# QSFP_Cages_Connectors.net
KiCad netlist of a schematic drawn in Altium Designer
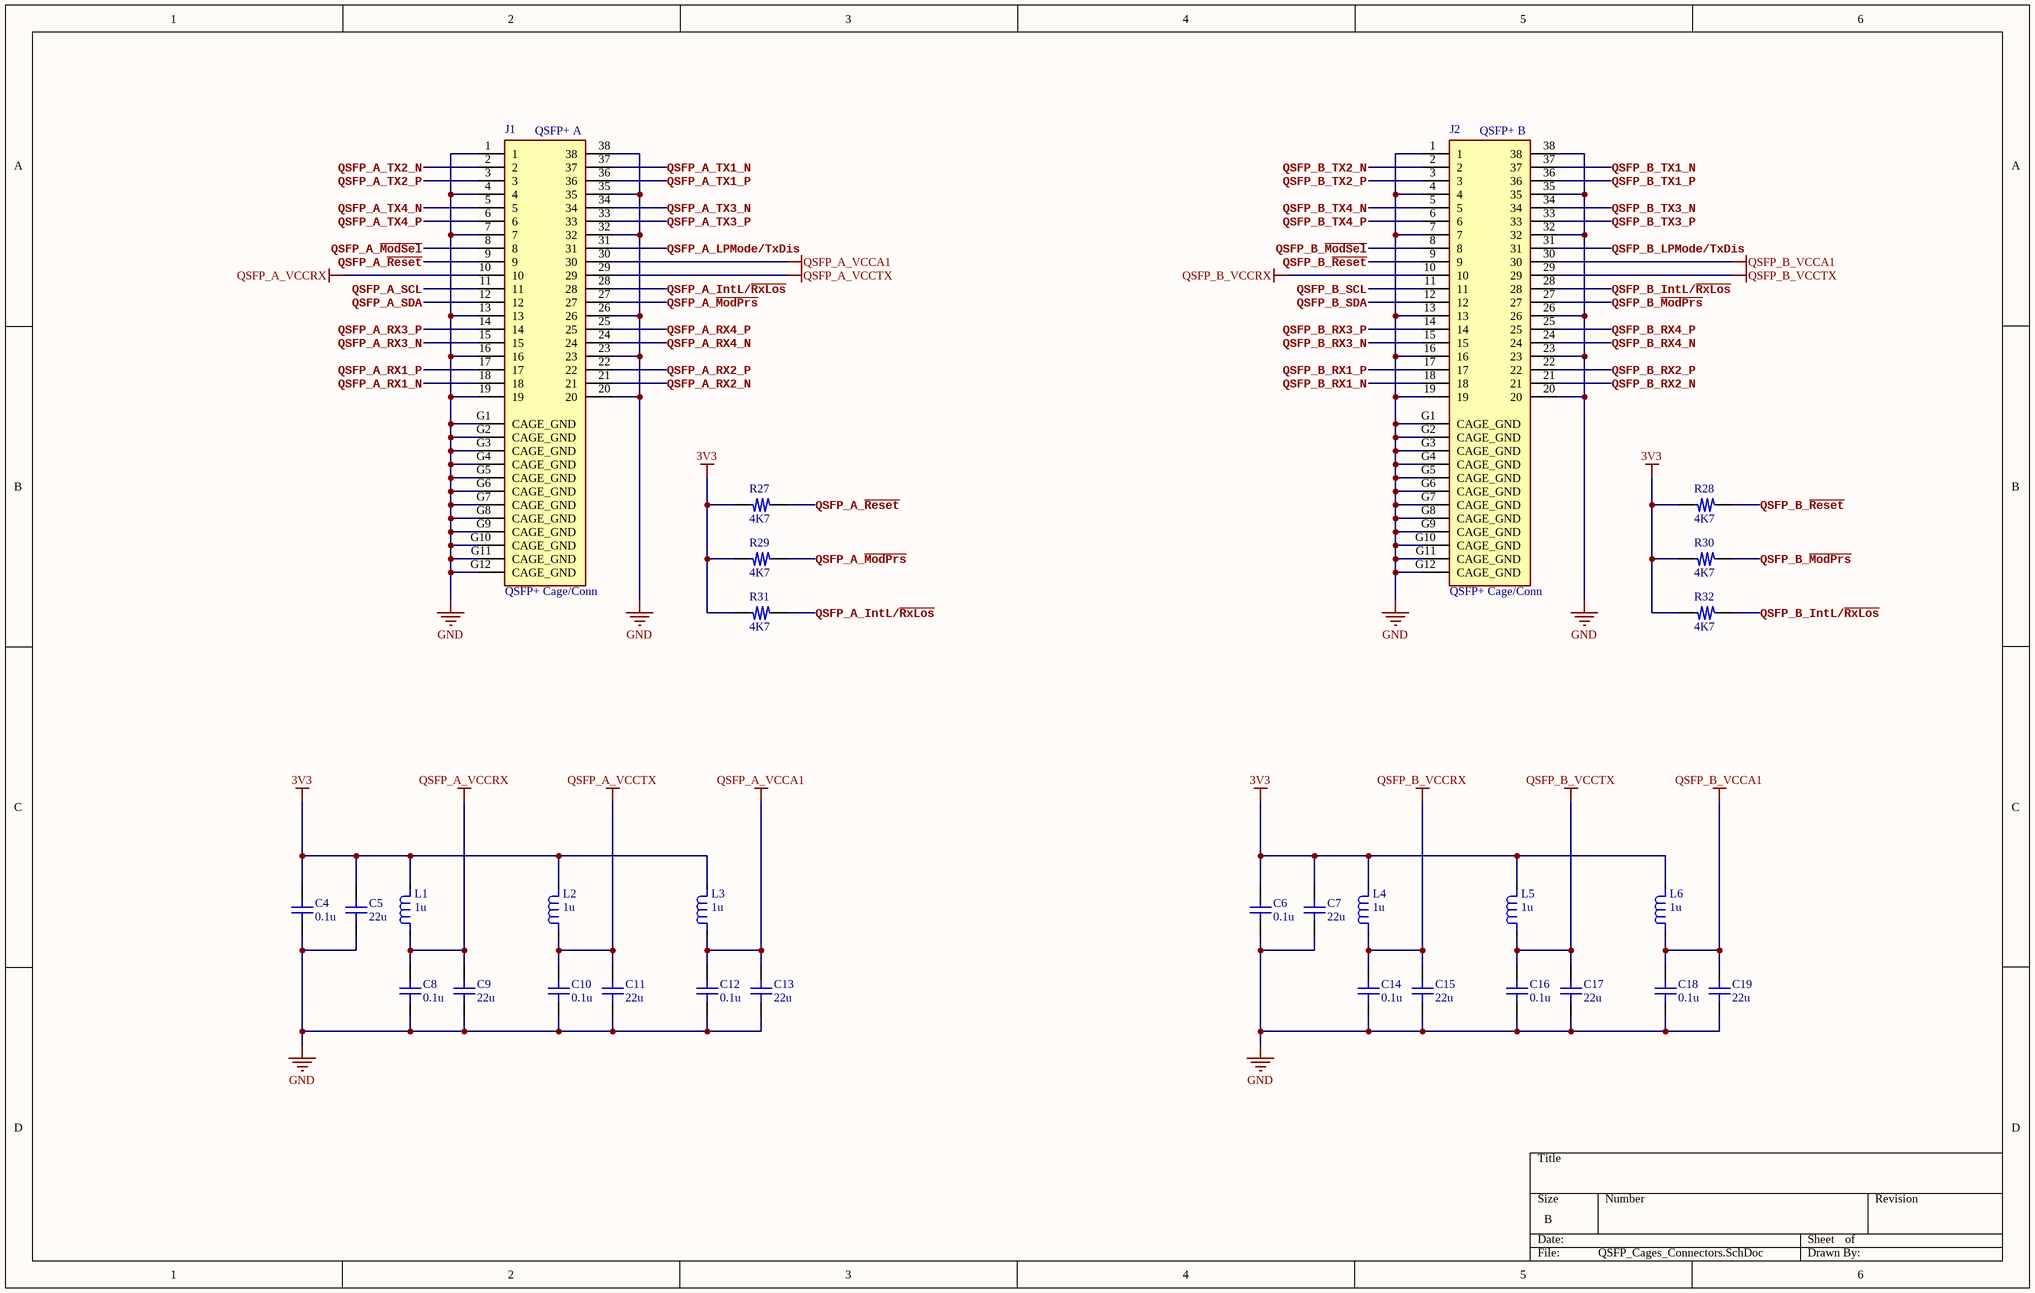
[diagram p0: QSFP_Cages_Connectors.SchDoc]

(export (version "E")
  (design (tool "Eeschema 10.0.6"))
  (components
    (comp (ref "C4")
      (value "0.1u")
      (footprint "C_0402_Generic")
      (description "0.1µF 16V X7R SMD ceramic capacitor in 0402 size")
      (fields
        (field (name "MANUFACTURER") "Murata Electronics")
        (field (name "MANUFACTURER PART NUMBER") "GRM155R71C104KA88D")
      )
      (libsource (lib "Capstone_Schematic_Library") (part "GRM155R71C104KA88D"))
    )
    (comp (ref "C5")
      (value "22u")
      (footprint "C_0603_Generic")
      (description "22µF 6.3V X5R SMD ceramic capacitor in 0603 size")
      (fields
        (field (name "MANUFACTURER") "Murata Electronics")
        (field (name "MANUFACTURER PART NUMBER") "GRM188R60J226MEA0D")
      )
      (libsource (lib "Capstone_Schematic_Library") (part "GRM188R60J226MEA0D"))
    )
    (comp (ref "C6")
      (value "0.1u")
      (footprint "C_0402_Generic")
      (description "0.1µF 16V X7R SMD ceramic capacitor in 0402 size")
      (fields
        (field (name "MANUFACTURER") "Murata Electronics")
        (field (name "MANUFACTURER PART NUMBER") "GRM155R71C104KA88D")
      )
      (libsource (lib "Capstone_Schematic_Library") (part "GRM155R71C104KA88D"))
    )
    (comp (ref "C7")
      (value "22u")
      (footprint "C_0603_Generic")
      (description "22µF 6.3V X5R SMD ceramic capacitor in 0603 size")
      (fields
        (field (name "MANUFACTURER") "Murata Electronics")
        (field (name "MANUFACTURER PART NUMBER") "GRM188R60J226MEA0D")
      )
      (libsource (lib "Capstone_Schematic_Library") (part "GRM188R60J226MEA0D"))
    )
    (comp (ref "C8")
      (value "0.1u")
      (footprint "C_0402_Generic")
      (description "0.1µF 16V X7R SMD ceramic capacitor in 0402 size")
      (fields
        (field (name "MANUFACTURER") "Murata Electronics")
        (field (name "MANUFACTURER PART NUMBER") "GRM155R71C104KA88D")
      )
      (libsource (lib "Capstone_Schematic_Library") (part "GRM155R71C104KA88D"))
    )
    (comp (ref "C9")
      (value "22u")
      (footprint "C_0603_Generic")
      (description "22µF 6.3V X5R SMD ceramic capacitor in 0603 size")
      (fields
        (field (name "MANUFACTURER") "Murata Electronics")
        (field (name "MANUFACTURER PART NUMBER") "GRM188R60J226MEA0D")
      )
      (libsource (lib "Capstone_Schematic_Library") (part "GRM188R60J226MEA0D"))
    )
    (comp (ref "C10")
      (value "0.1u")
      (footprint "C_0402_Generic")
      (description "0.1µF 16V X7R SMD ceramic capacitor in 0402 size")
      (fields
        (field (name "MANUFACTURER") "Murata Electronics")
        (field (name "MANUFACTURER PART NUMBER") "GRM155R71C104KA88D")
      )
      (libsource (lib "Capstone_Schematic_Library") (part "GRM155R71C104KA88D"))
    )
    (comp (ref "C11")
      (value "22u")
      (footprint "C_0603_Generic")
      (description "22µF 6.3V X5R SMD ceramic capacitor in 0603 size")
      (fields
        (field (name "MANUFACTURER") "Murata Electronics")
        (field (name "MANUFACTURER PART NUMBER") "GRM188R60J226MEA0D")
      )
      (libsource (lib "Capstone_Schematic_Library") (part "GRM188R60J226MEA0D"))
    )
    (comp (ref "C12")
      (value "0.1u")
      (footprint "C_0402_Generic")
      (description "0.1µF 16V X7R SMD ceramic capacitor in 0402 size")
      (fields
        (field (name "MANUFACTURER") "Murata Electronics")
        (field (name "MANUFACTURER PART NUMBER") "GRM155R71C104KA88D")
      )
      (libsource (lib "Capstone_Schematic_Library") (part "GRM155R71C104KA88D"))
    )
    (comp (ref "C13")
      (value "22u")
      (footprint "C_0603_Generic")
      (description "22µF 6.3V X5R SMD ceramic capacitor in 0603 size")
      (fields
        (field (name "MANUFACTURER") "Murata Electronics")
        (field (name "MANUFACTURER PART NUMBER") "GRM188R60J226MEA0D")
      )
      (libsource (lib "Capstone_Schematic_Library") (part "GRM188R60J226MEA0D"))
    )
    (comp (ref "C14")
      (value "0.1u")
      (footprint "C_0402_Generic")
      (description "0.1µF 16V X7R SMD ceramic capacitor in 0402 size")
      (fields
        (field (name "MANUFACTURER") "Murata Electronics")
        (field (name "MANUFACTURER PART NUMBER") "GRM155R71C104KA88D")
      )
      (libsource (lib "Capstone_Schematic_Library") (part "GRM155R71C104KA88D"))
    )
    (comp (ref "C15")
      (value "22u")
      (footprint "C_0603_Generic")
      (description "22µF 6.3V X5R SMD ceramic capacitor in 0603 size")
      (fields
        (field (name "MANUFACTURER") "Murata Electronics")
        (field (name "MANUFACTURER PART NUMBER") "GRM188R60J226MEA0D")
      )
      (libsource (lib "Capstone_Schematic_Library") (part "GRM188R60J226MEA0D"))
    )
    (comp (ref "C16")
      (value "0.1u")
      (footprint "C_0402_Generic")
      (description "0.1µF 16V X7R SMD ceramic capacitor in 0402 size")
      (fields
        (field (name "MANUFACTURER") "Murata Electronics")
        (field (name "MANUFACTURER PART NUMBER") "GRM155R71C104KA88D")
      )
      (libsource (lib "Capstone_Schematic_Library") (part "GRM155R71C104KA88D"))
    )
    (comp (ref "C17")
      (value "22u")
      (footprint "C_0603_Generic")
      (description "22µF 6.3V X5R SMD ceramic capacitor in 0603 size")
      (fields
        (field (name "MANUFACTURER") "Murata Electronics")
        (field (name "MANUFACTURER PART NUMBER") "GRM188R60J226MEA0D")
      )
      (libsource (lib "Capstone_Schematic_Library") (part "GRM188R60J226MEA0D"))
    )
    (comp (ref "C18")
      (value "0.1u")
      (footprint "C_0402_Generic")
      (description "0.1µF 16V X7R SMD ceramic capacitor in 0402 size")
      (fields
        (field (name "MANUFACTURER") "Murata Electronics")
        (field (name "MANUFACTURER PART NUMBER") "GRM155R71C104KA88D")
      )
      (libsource (lib "Capstone_Schematic_Library") (part "GRM155R71C104KA88D"))
    )
    (comp (ref "C19")
      (value "22u")
      (footprint "C_0603_Generic")
      (description "22µF 6.3V X5R SMD ceramic capacitor in 0603 size")
      (fields
        (field (name "MANUFACTURER") "Murata Electronics")
        (field (name "MANUFACTURER PART NUMBER") "GRM188R60J226MEA0D")
      )
      (libsource (lib "Capstone_Schematic_Library") (part "GRM188R60J226MEA0D"))
    )
    (comp (ref "J1")
      (value "QSFP+ Cage/Conn")
      (footprint "AMPHENOL_U95T151100A")
      (description "NOTE: Notes Also uses one FS1-Z38-20Z6-60. 38 Position QSFP+ Receptacle")
      (fields (field (name "MP") "U95T151100A") (field (name "MF") "Amphenol"))
      (libsource (lib "Capstone_Schematic_Library") (part "U95T151100A"))
    )
    (comp (ref "J2")
      (value "QSFP+ Cage/Conn")
      (footprint "AMPHENOL_U95T151100A")
      (description "NOTE: Notes Also uses one FS1-Z38-20Z6-60. 38 Position QSFP+ Receptacle")
      (fields (field (name "MP") "U95T151100A") (field (name "MF") "Amphenol"))
      (libsource (lib "Capstone_Schematic_Library") (part "U95T151100A"))
    )
    (comp (ref "L1")
      (value "1u")
      (footprint "Murata_Ind_1008")
      (description "1µH Shielded 3.3A 40mOhm 1008 Inductor")
      (fields
        (field (name "MANUFACTURER") "Murata Electronics")
        (field (name "MANUFACTURER PART NUMBER") "DFE252012F-1R0M=P2")
      )
      (libsource (lib "Capstone_Schematic_Library") (part "DFE252012F-1R0M=P2"))
    )
    (comp (ref "L2")
      (value "1u")
      (footprint "Murata_Ind_1008")
      (description "1µH Shielded 3.3A 40mOhm 1008 Inductor")
      (fields
        (field (name "MANUFACTURER") "Murata Electronics")
        (field (name "MANUFACTURER PART NUMBER") "DFE252012F-1R0M=P2")
      )
      (libsource (lib "Capstone_Schematic_Library") (part "DFE252012F-1R0M=P2"))
    )
    (comp (ref "L3")
      (value "1u")
      (footprint "Murata_Ind_1008")
      (description "1µH Shielded 3.3A 40mOhm 1008 Inductor")
      (fields
        (field (name "MANUFACTURER") "Murata Electronics")
        (field (name "MANUFACTURER PART NUMBER") "DFE252012F-1R0M=P2")
      )
      (libsource (lib "Capstone_Schematic_Library") (part "DFE252012F-1R0M=P2"))
    )
    (comp (ref "L4")
      (value "1u")
      (footprint "Murata_Ind_1008")
      (description "1µH Shielded 3.3A 40mOhm 1008 Inductor")
      (fields
        (field (name "MANUFACTURER") "Murata Electronics")
        (field (name "MANUFACTURER PART NUMBER") "DFE252012F-1R0M=P2")
      )
      (libsource (lib "Capstone_Schematic_Library") (part "DFE252012F-1R0M=P2"))
    )
    (comp (ref "L5")
      (value "1u")
      (footprint "Murata_Ind_1008")
      (description "1µH Shielded 3.3A 40mOhm 1008 Inductor")
      (fields
        (field (name "MANUFACTURER") "Murata Electronics")
        (field (name "MANUFACTURER PART NUMBER") "DFE252012F-1R0M=P2")
      )
      (libsource (lib "Capstone_Schematic_Library") (part "DFE252012F-1R0M=P2"))
    )
    (comp (ref "L6")
      (value "1u")
      (footprint "Murata_Ind_1008")
      (description "1µH Shielded 3.3A 40mOhm 1008 Inductor")
      (fields
        (field (name "MANUFACTURER") "Murata Electronics")
        (field (name "MANUFACTURER PART NUMBER") "DFE252012F-1R0M=P2")
      )
      (libsource (lib "Capstone_Schematic_Library") (part "DFE252012F-1R0M=P2"))
    )
    (comp (ref "R27")
      (value "4K7")
      (footprint "R_0402_Generic")
      (description "4.7KOhm 1% 1/10W SMD resistor in 0402 size")
      (fields
        (field (name "MANUFACTURER") "Panasonic")
        (field (name "MANUFACTURER PART NUMBER") "ERJ-2RKF4701X")
      )
      (libsource (lib "Capstone_Schematic_Library") (part "ERJ-2RKF4701X"))
    )
    (comp (ref "R28")
      (value "4K7")
      (footprint "R_0402_Generic")
      (description "4.7KOhm 1% 1/10W SMD resistor in 0402 size")
      (fields
        (field (name "MANUFACTURER") "Panasonic")
        (field (name "MANUFACTURER PART NUMBER") "ERJ-2RKF4701X")
      )
      (libsource (lib "Capstone_Schematic_Library") (part "ERJ-2RKF4701X"))
    )
    (comp (ref "R29")
      (value "4K7")
      (footprint "R_0402_Generic")
      (description "4.7KOhm 1% 1/10W SMD resistor in 0402 size")
      (fields
        (field (name "MANUFACTURER") "Panasonic")
        (field (name "MANUFACTURER PART NUMBER") "ERJ-2RKF4701X")
      )
      (libsource (lib "Capstone_Schematic_Library") (part "ERJ-2RKF4701X"))
    )
    (comp (ref "R30")
      (value "4K7")
      (footprint "R_0402_Generic")
      (description "4.7KOhm 1% 1/10W SMD resistor in 0402 size")
      (fields
        (field (name "MANUFACTURER") "Panasonic")
        (field (name "MANUFACTURER PART NUMBER") "ERJ-2RKF4701X")
      )
      (libsource (lib "Capstone_Schematic_Library") (part "ERJ-2RKF4701X"))
    )
    (comp (ref "R31")
      (value "4K7")
      (footprint "R_0402_Generic")
      (description "4.7KOhm 1% 1/10W SMD resistor in 0402 size")
      (fields
        (field (name "MANUFACTURER") "Panasonic")
        (field (name "MANUFACTURER PART NUMBER") "ERJ-2RKF4701X")
      )
      (libsource (lib "Capstone_Schematic_Library") (part "ERJ-2RKF4701X"))
    )
    (comp (ref "R32")
      (value "4K7")
      (footprint "R_0402_Generic")
      (description "4.7KOhm 1% 1/10W SMD resistor in 0402 size")
      (fields
        (field (name "MANUFACTURER") "Panasonic")
        (field (name "MANUFACTURER PART NUMBER") "ERJ-2RKF4701X")
      )
      (libsource (lib "Capstone_Schematic_Library") (part "ERJ-2RKF4701X"))
    )
  )
  (nets
    (net (code "1") (name "/QSFP_A_IntL{slash}~{RxLos}") (class "Default")
      (node (ref "J1") (pin "28") (pinfunction "28_28") (pintype "passive"))
      (node (ref "R31") (pin "1") (pinfunction "1_1") (pintype "passive"))
    )
    (net (code "2") (name "/QSFP_A_LPMode{slash}TxDis") (class "Default")
      (node (ref "J1") (pin "31") (pinfunction "31_31") (pintype "passive"))
    )
    (net (code "3") (name "/QSFP_A_RX1_N") (class "Default")
      (node (ref "J1") (pin "18") (pinfunction "18_18") (pintype "passive"))
    )
    (net (code "4") (name "/QSFP_A_RX1_P") (class "Default")
      (node (ref "J1") (pin "17") (pinfunction "17_17") (pintype "passive"))
    )
    (net (code "5") (name "/QSFP_A_RX2_N") (class "Default")
      (node (ref "J1") (pin "21") (pinfunction "21_21") (pintype "passive"))
    )
    (net (code "6") (name "/QSFP_A_RX2_P") (class "Default")
      (node (ref "J1") (pin "22") (pinfunction "22_22") (pintype "passive"))
    )
    (net (code "7") (name "/QSFP_A_RX3_N") (class "Default")
      (node (ref "J1") (pin "15") (pinfunction "15_15") (pintype "passive"))
    )
    (net (code "8") (name "/QSFP_A_RX3_P") (class "Default")
      (node (ref "J1") (pin "14") (pinfunction "14_14") (pintype "passive"))
    )
    (net (code "9") (name "/QSFP_A_RX4_N") (class "Default")
      (node (ref "J1") (pin "24") (pinfunction "24_24") (pintype "passive"))
    )
    (net (code "10") (name "/QSFP_A_RX4_P") (class "Default")
      (node (ref "J1") (pin "25") (pinfunction "25_25") (pintype "passive"))
    )
    (net (code "11") (name "/QSFP_A_SCL") (class "Default")
      (node (ref "J1") (pin "11") (pinfunction "11_11") (pintype "passive"))
    )
    (net (code "12") (name "/QSFP_A_SDA") (class "Default")
      (node (ref "J1") (pin "12") (pinfunction "12_12") (pintype "passive"))
    )
    (net (code "13") (name "/QSFP_A_TX1_N") (class "Default")
      (node (ref "J1") (pin "37") (pinfunction "37_37") (pintype "passive"))
    )
    (net (code "14") (name "/QSFP_A_TX1_P") (class "Default")
      (node (ref "J1") (pin "36") (pinfunction "36_36") (pintype "passive"))
    )
    (net (code "15") (name "/QSFP_A_TX2_N") (class "Default")
      (node (ref "J1") (pin "2") (pinfunction "2_2") (pintype "passive"))
    )
    (net (code "16") (name "/QSFP_A_TX2_P") (class "Default")
      (node (ref "J1") (pin "3") (pinfunction "3_3") (pintype "passive"))
    )
    (net (code "17") (name "/QSFP_A_TX3_N") (class "Default")
      (node (ref "J1") (pin "34") (pinfunction "34_34") (pintype "passive"))
    )
    (net (code "18") (name "/QSFP_A_TX3_P") (class "Default")
      (node (ref "J1") (pin "33") (pinfunction "33_33") (pintype "passive"))
    )
    (net (code "19") (name "/QSFP_A_TX4_N") (class "Default")
      (node (ref "J1") (pin "5") (pinfunction "5_5") (pintype "passive"))
    )
    (net (code "20") (name "/QSFP_A_TX4_P") (class "Default")
      (node (ref "J1") (pin "6") (pinfunction "6_6") (pintype "passive"))
    )
    (net (code "21") (name "/QSFP_A_~{ModPrs}") (class "Default")
      (node (ref "J1") (pin "27") (pinfunction "27_27") (pintype "passive"))
      (node (ref "R29") (pin "1") (pinfunction "1_1") (pintype "passive"))
    )
    (net (code "22") (name "/QSFP_A_~{ModSel}") (class "Default")
      (node (ref "J1") (pin "8") (pinfunction "8_8") (pintype "passive"))
    )
    (net (code "23") (name "/QSFP_A_~{Reset}") (class "Default")
      (node (ref "J1") (pin "9") (pinfunction "9_9") (pintype "passive"))
      (node (ref "R27") (pin "1") (pinfunction "1_1") (pintype "passive"))
    )
    (net (code "24") (name "/QSFP_B_IntL{slash}~{RxLos}") (class "Default")
      (node (ref "J2") (pin "28") (pinfunction "28_28") (pintype "passive"))
      (node (ref "R32") (pin "1") (pinfunction "1_1") (pintype "passive"))
    )
    (net (code "25") (name "/QSFP_B_LPMode{slash}TxDis") (class "Default")
      (node (ref "J2") (pin "31") (pinfunction "31_31") (pintype "passive"))
    )
    (net (code "26") (name "/QSFP_B_RX1_N") (class "Default")
      (node (ref "J2") (pin "18") (pinfunction "18_18") (pintype "passive"))
    )
    (net (code "27") (name "/QSFP_B_RX1_P") (class "Default")
      (node (ref "J2") (pin "17") (pinfunction "17_17") (pintype "passive"))
    )
    (net (code "28") (name "/QSFP_B_RX2_N") (class "Default")
      (node (ref "J2") (pin "21") (pinfunction "21_21") (pintype "passive"))
    )
    (net (code "29") (name "/QSFP_B_RX2_P") (class "Default")
      (node (ref "J2") (pin "22") (pinfunction "22_22") (pintype "passive"))
    )
    (net (code "30") (name "/QSFP_B_RX3_N") (class "Default")
      (node (ref "J2") (pin "15") (pinfunction "15_15") (pintype "passive"))
    )
    (net (code "31") (name "/QSFP_B_RX3_P") (class "Default")
      (node (ref "J2") (pin "14") (pinfunction "14_14") (pintype "passive"))
    )
    (net (code "32") (name "/QSFP_B_RX4_N") (class "Default")
      (node (ref "J2") (pin "24") (pinfunction "24_24") (pintype "passive"))
    )
    (net (code "33") (name "/QSFP_B_RX4_P") (class "Default")
      (node (ref "J2") (pin "25") (pinfunction "25_25") (pintype "passive"))
    )
    (net (code "34") (name "/QSFP_B_SCL") (class "Default")
      (node (ref "J2") (pin "11") (pinfunction "11_11") (pintype "passive"))
    )
    (net (code "35") (name "/QSFP_B_SDA") (class "Default")
      (node (ref "J2") (pin "12") (pinfunction "12_12") (pintype "passive"))
    )
    (net (code "36") (name "/QSFP_B_TX1_N") (class "Default")
      (node (ref "J2") (pin "37") (pinfunction "37_37") (pintype "passive"))
    )
    (net (code "37") (name "/QSFP_B_TX1_P") (class "Default")
      (node (ref "J2") (pin "36") (pinfunction "36_36") (pintype "passive"))
    )
    (net (code "38") (name "/QSFP_B_TX2_N") (class "Default")
      (node (ref "J2") (pin "2") (pinfunction "2_2") (pintype "passive"))
    )
    (net (code "39") (name "/QSFP_B_TX2_P") (class "Default")
      (node (ref "J2") (pin "3") (pinfunction "3_3") (pintype "passive"))
    )
    (net (code "40") (name "/QSFP_B_TX3_N") (class "Default")
      (node (ref "J2") (pin "34") (pinfunction "34_34") (pintype "passive"))
    )
    (net (code "41") (name "/QSFP_B_TX3_P") (class "Default")
      (node (ref "J2") (pin "33") (pinfunction "33_33") (pintype "passive"))
    )
    (net (code "42") (name "/QSFP_B_TX4_N") (class "Default")
      (node (ref "J2") (pin "5") (pinfunction "5_5") (pintype "passive"))
    )
    (net (code "43") (name "/QSFP_B_TX4_P") (class "Default")
      (node (ref "J2") (pin "6") (pinfunction "6_6") (pintype "passive"))
    )
    (net (code "44") (name "/QSFP_B_~{ModPrs}") (class "Default")
      (node (ref "J2") (pin "27") (pinfunction "27_27") (pintype "passive"))
      (node (ref "R30") (pin "1") (pinfunction "1_1") (pintype "passive"))
    )
    (net (code "45") (name "/QSFP_B_~{ModSel}") (class "Default")
      (node (ref "J2") (pin "8") (pinfunction "8_8") (pintype "passive"))
    )
    (net (code "46") (name "/QSFP_B_~{Reset}") (class "Default")
      (node (ref "J2") (pin "9") (pinfunction "9_9") (pintype "passive"))
      (node (ref "R28") (pin "1") (pinfunction "1_1") (pintype "passive"))
    )
    (net (code "47") (name "3V3") (class "Default")
      (node (ref "C4") (pin "2") (pinfunction "2_2") (pintype "passive"))
      (node (ref "C5") (pin "2") (pinfunction "2_2") (pintype "passive"))
      (node (ref "C6") (pin "2") (pinfunction "2_2") (pintype "passive"))
      (node (ref "C7") (pin "2") (pinfunction "2_2") (pintype "passive"))
      (node (ref "L1") (pin "1") (pinfunction "1_1") (pintype "passive"))
      (node (ref "L2") (pin "1") (pinfunction "1_1") (pintype "passive"))
      (node (ref "L3") (pin "1") (pinfunction "1_1") (pintype "passive"))
      (node (ref "L4") (pin "1") (pinfunction "1_1") (pintype "passive"))
      (node (ref "L5") (pin "1") (pinfunction "1_1") (pintype "passive"))
      (node (ref "L6") (pin "1") (pinfunction "1_1") (pintype "passive"))
      (node (ref "R27") (pin "2") (pinfunction "2_2") (pintype "passive"))
      (node (ref "R28") (pin "2") (pinfunction "2_2") (pintype "passive"))
      (node (ref "R29") (pin "2") (pinfunction "2_2") (pintype "passive"))
      (node (ref "R30") (pin "2") (pinfunction "2_2") (pintype "passive"))
      (node (ref "R31") (pin "2") (pinfunction "2_2") (pintype "passive"))
      (node (ref "R32") (pin "2") (pinfunction "2_2") (pintype "passive"))
    )
    (net (code "48") (name "GND") (class "Default")
      (node (ref "C10") (pin "1") (pinfunction "1_1") (pintype "passive"))
      (node (ref "C11") (pin "1") (pinfunction "1_1") (pintype "passive"))
      (node (ref "C12") (pin "1") (pinfunction "1_1") (pintype "passive"))
      (node (ref "C13") (pin "1") (pinfunction "1_1") (pintype "passive"))
      (node (ref "C14") (pin "1") (pinfunction "1_1") (pintype "passive"))
      (node (ref "C15") (pin "1") (pinfunction "1_1") (pintype "passive"))
      (node (ref "C16") (pin "1") (pinfunction "1_1") (pintype "passive"))
      (node (ref "C17") (pin "1") (pinfunction "1_1") (pintype "passive"))
      (node (ref "C18") (pin "1") (pinfunction "1_1") (pintype "passive"))
      (node (ref "C19") (pin "1") (pinfunction "1_1") (pintype "passive"))
      (node (ref "C4") (pin "1") (pinfunction "1_1") (pintype "passive"))
      (node (ref "C5") (pin "1") (pinfunction "1_1") (pintype "passive"))
      (node (ref "C6") (pin "1") (pinfunction "1_1") (pintype "passive"))
      (node (ref "C7") (pin "1") (pinfunction "1_1") (pintype "passive"))
      (node (ref "C8") (pin "1") (pinfunction "1_1") (pintype "passive"))
      (node (ref "C9") (pin "1") (pinfunction "1_1") (pintype "passive"))
      (node (ref "J1") (pin "1") (pinfunction "1_1") (pintype "passive"))
      (node (ref "J1") (pin "13") (pinfunction "13_13") (pintype "passive"))
      (node (ref "J1") (pin "16") (pinfunction "16_16") (pintype "passive"))
      (node (ref "J1") (pin "19") (pinfunction "19_19") (pintype "passive"))
      (node (ref "J1") (pin "20") (pinfunction "20_20") (pintype "passive"))
      (node (ref "J1") (pin "23") (pinfunction "23_23") (pintype "passive"))
      (node (ref "J1") (pin "26") (pinfunction "26_26") (pintype "passive"))
      (node (ref "J1") (pin "32") (pinfunction "32_32") (pintype "passive"))
      (node (ref "J1") (pin "35") (pinfunction "35_35") (pintype "passive"))
      (node (ref "J1") (pin "38") (pinfunction "38_38") (pintype "passive"))
      (node (ref "J1") (pin "4") (pinfunction "4_4") (pintype "passive"))
      (node (ref "J1") (pin "7") (pinfunction "7_7") (pintype "passive"))
      (node (ref "J1") (pin "G1") (pinfunction "CAGE_GND_G1") (pintype "power_in"))
      (node (ref "J1") (pin "G10") (pinfunction "CAGE_GND_G10") (pintype "power_in"))
      (node (ref "J1") (pin "G11") (pinfunction "CAGE_GND_G11") (pintype "power_in"))
      (node (ref "J1") (pin "G12") (pinfunction "CAGE_GND_G12") (pintype "power_in"))
      (node (ref "J1") (pin "G2") (pinfunction "CAGE_GND_G2") (pintype "power_in"))
      (node (ref "J1") (pin "G3") (pinfunction "CAGE_GND_G3") (pintype "power_in"))
      (node (ref "J1") (pin "G4") (pinfunction "CAGE_GND_G4") (pintype "power_in"))
      (node (ref "J1") (pin "G5") (pinfunction "CAGE_GND_G5") (pintype "power_in"))
      (node (ref "J1") (pin "G6") (pinfunction "CAGE_GND_G6") (pintype "power_in"))
      (node (ref "J1") (pin "G7") (pinfunction "CAGE_GND_G7") (pintype "power_in"))
      (node (ref "J1") (pin "G8") (pinfunction "CAGE_GND_G8") (pintype "power_in"))
      (node (ref "J1") (pin "G9") (pinfunction "CAGE_GND_G9") (pintype "power_in"))
      (node (ref "J2") (pin "1") (pinfunction "1_1") (pintype "passive"))
      (node (ref "J2") (pin "13") (pinfunction "13_13") (pintype "passive"))
      (node (ref "J2") (pin "16") (pinfunction "16_16") (pintype "passive"))
      (node (ref "J2") (pin "19") (pinfunction "19_19") (pintype "passive"))
      (node (ref "J2") (pin "20") (pinfunction "20_20") (pintype "passive"))
      (node (ref "J2") (pin "23") (pinfunction "23_23") (pintype "passive"))
      (node (ref "J2") (pin "26") (pinfunction "26_26") (pintype "passive"))
      (node (ref "J2") (pin "32") (pinfunction "32_32") (pintype "passive"))
      (node (ref "J2") (pin "35") (pinfunction "35_35") (pintype "passive"))
      (node (ref "J2") (pin "38") (pinfunction "38_38") (pintype "passive"))
      (node (ref "J2") (pin "4") (pinfunction "4_4") (pintype "passive"))
      (node (ref "J2") (pin "7") (pinfunction "7_7") (pintype "passive"))
      (node (ref "J2") (pin "G1") (pinfunction "CAGE_GND_G1") (pintype "power_in"))
      (node (ref "J2") (pin "G10") (pinfunction "CAGE_GND_G10") (pintype "power_in"))
      (node (ref "J2") (pin "G11") (pinfunction "CAGE_GND_G11") (pintype "power_in"))
      (node (ref "J2") (pin "G12") (pinfunction "CAGE_GND_G12") (pintype "power_in"))
      (node (ref "J2") (pin "G2") (pinfunction "CAGE_GND_G2") (pintype "power_in"))
      (node (ref "J2") (pin "G3") (pinfunction "CAGE_GND_G3") (pintype "power_in"))
      (node (ref "J2") (pin "G4") (pinfunction "CAGE_GND_G4") (pintype "power_in"))
      (node (ref "J2") (pin "G5") (pinfunction "CAGE_GND_G5") (pintype "power_in"))
      (node (ref "J2") (pin "G6") (pinfunction "CAGE_GND_G6") (pintype "power_in"))
      (node (ref "J2") (pin "G7") (pinfunction "CAGE_GND_G7") (pintype "power_in"))
      (node (ref "J2") (pin "G8") (pinfunction "CAGE_GND_G8") (pintype "power_in"))
      (node (ref "J2") (pin "G9") (pinfunction "CAGE_GND_G9") (pintype "power_in"))
    )
    (net (code "49") (name "QSFP_A_VCCA1") (class "Default")
      (node (ref "C12") (pin "2") (pinfunction "2_2") (pintype "passive"))
      (node (ref "C13") (pin "2") (pinfunction "2_2") (pintype "passive"))
      (node (ref "J1") (pin "30") (pinfunction "30_30") (pintype "passive"))
      (node (ref "L3") (pin "2") (pinfunction "2_2") (pintype "passive"))
    )
    (net (code "50") (name "QSFP_A_VCCRX") (class "Default")
      (node (ref "C8") (pin "2") (pinfunction "2_2") (pintype "passive"))
      (node (ref "C9") (pin "2") (pinfunction "2_2") (pintype "passive"))
      (node (ref "J1") (pin "10") (pinfunction "10_10") (pintype "passive"))
      (node (ref "L1") (pin "2") (pinfunction "2_2") (pintype "passive"))
    )
    (net (code "51") (name "QSFP_A_VCCTX") (class "Default")
      (node (ref "C10") (pin "2") (pinfunction "2_2") (pintype "passive"))
      (node (ref "C11") (pin "2") (pinfunction "2_2") (pintype "passive"))
      (node (ref "J1") (pin "29") (pinfunction "29_29") (pintype "passive"))
      (node (ref "L2") (pin "2") (pinfunction "2_2") (pintype "passive"))
    )
    (net (code "52") (name "QSFP_B_VCCA1") (class "Default")
      (node (ref "C18") (pin "2") (pinfunction "2_2") (pintype "passive"))
      (node (ref "C19") (pin "2") (pinfunction "2_2") (pintype "passive"))
      (node (ref "J2") (pin "30") (pinfunction "30_30") (pintype "passive"))
      (node (ref "L6") (pin "2") (pinfunction "2_2") (pintype "passive"))
    )
    (net (code "53") (name "QSFP_B_VCCRX") (class "Default")
      (node (ref "C14") (pin "2") (pinfunction "2_2") (pintype "passive"))
      (node (ref "C15") (pin "2") (pinfunction "2_2") (pintype "passive"))
      (node (ref "J2") (pin "10") (pinfunction "10_10") (pintype "passive"))
      (node (ref "L4") (pin "2") (pinfunction "2_2") (pintype "passive"))
    )
    (net (code "54") (name "QSFP_B_VCCTX") (class "Default")
      (node (ref "C16") (pin "2") (pinfunction "2_2") (pintype "passive"))
      (node (ref "C17") (pin "2") (pinfunction "2_2") (pintype "passive"))
      (node (ref "J2") (pin "29") (pinfunction "29_29") (pintype "passive"))
      (node (ref "L5") (pin "2") (pinfunction "2_2") (pintype "passive"))
    )
  )
)
